# Vario_Kobo.net
KiCad netlist of a schematic drawn in EAGLE
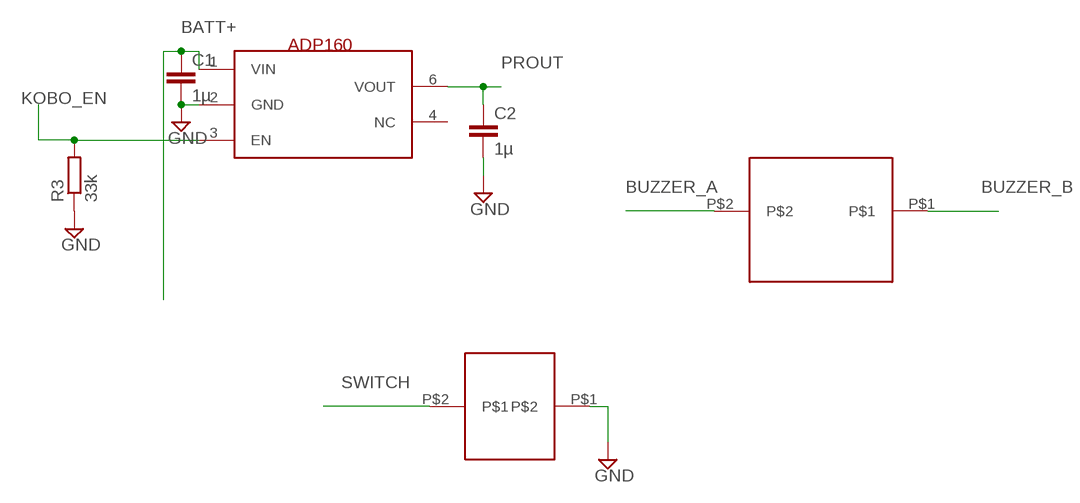
[diagram p0: schematic, sheet 1]
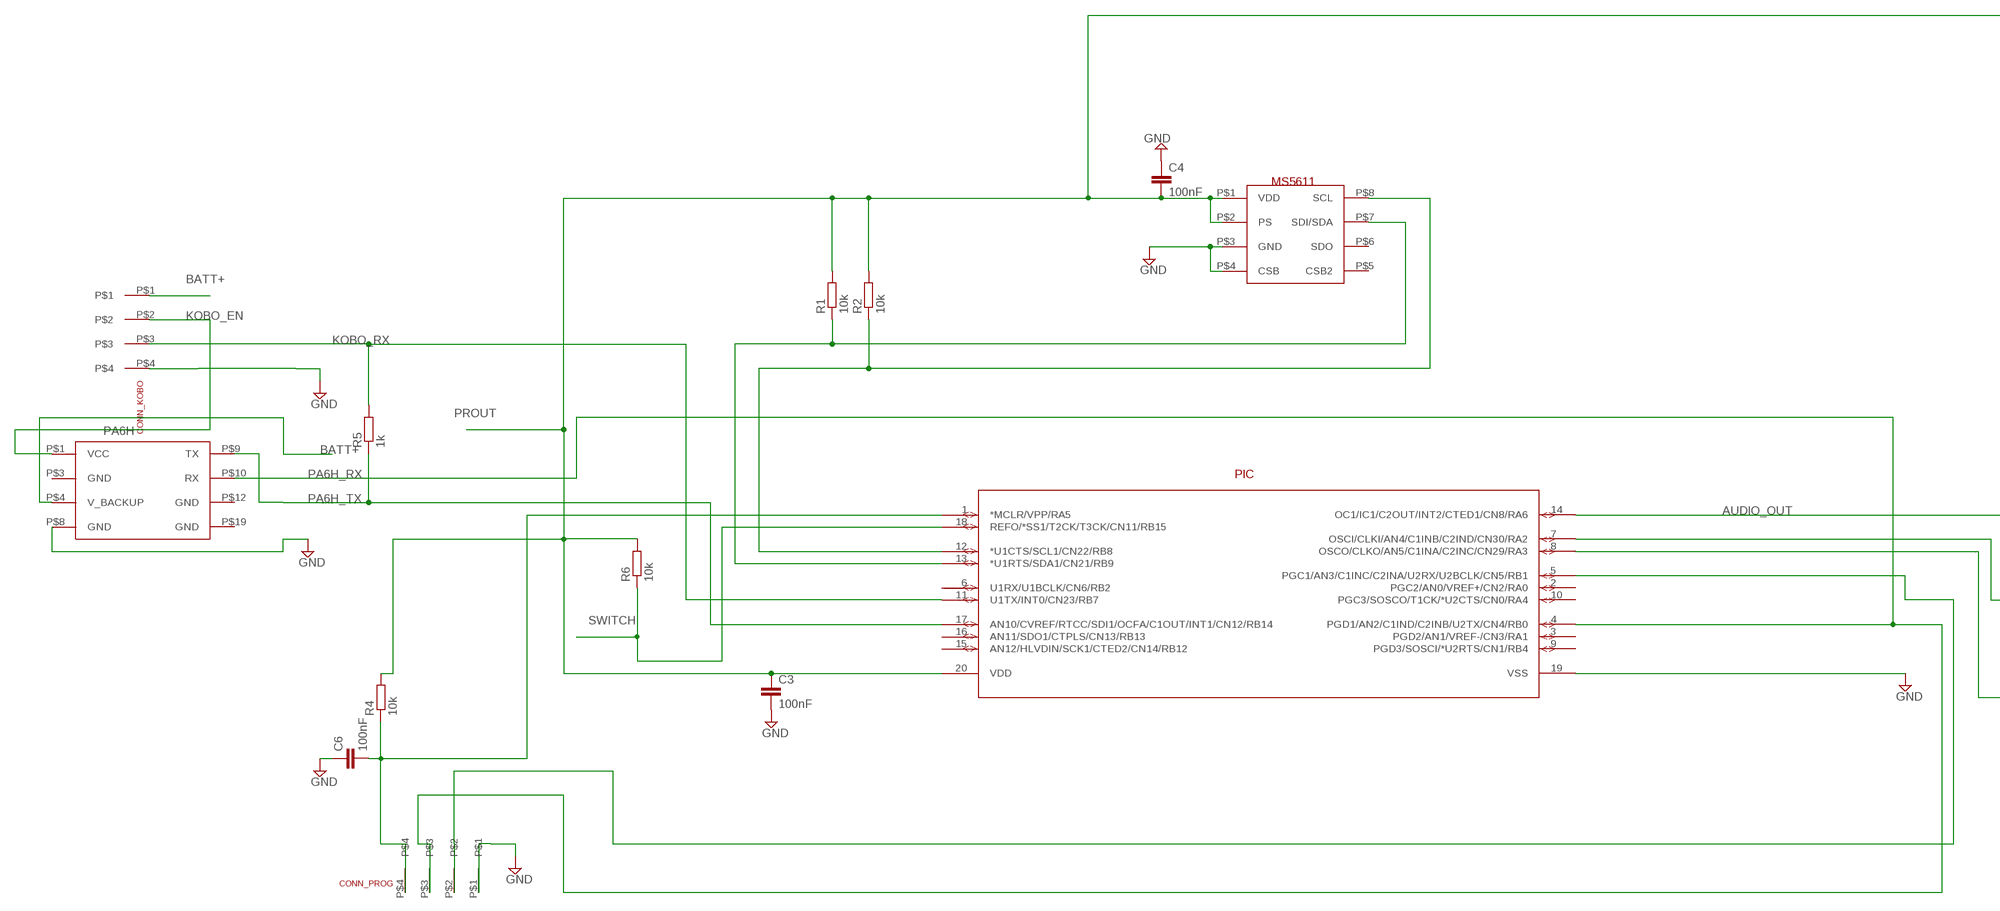
[diagram p1: schematic, sheet 2, part 1 of 2]
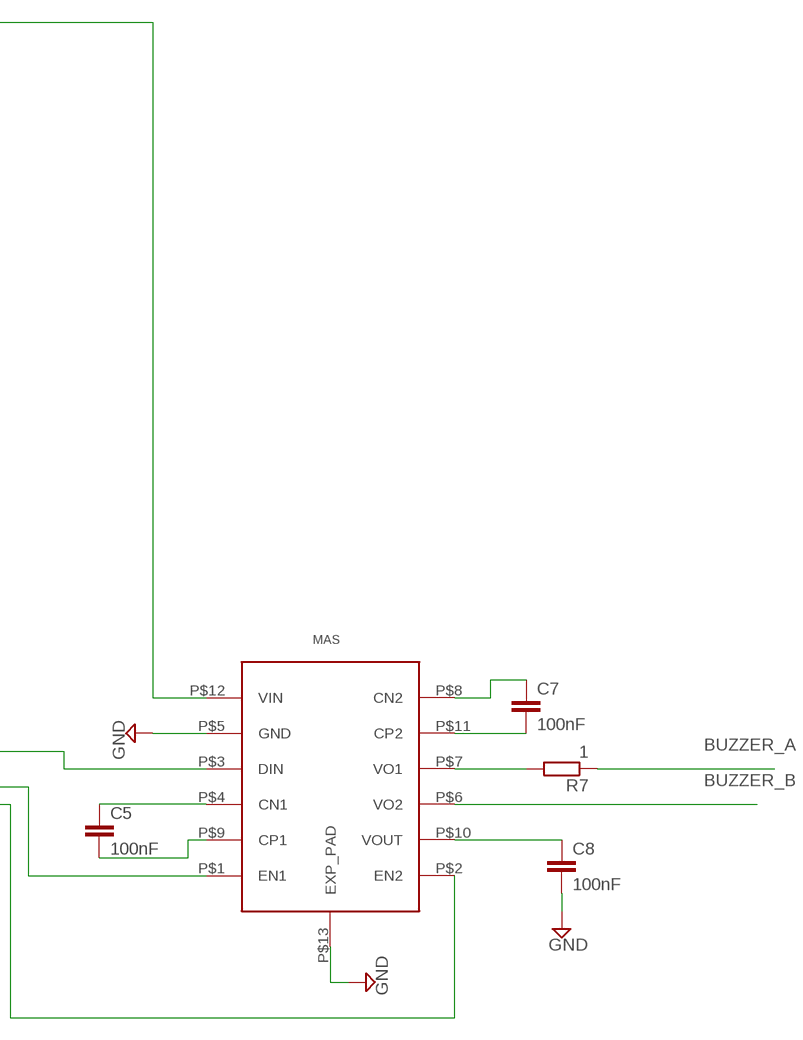
[diagram p2: schematic, sheet 2, part 2 of 2]

(export (version "E")
  (design (tool "Eeschema 10.0.6"))
  (components
    (comp (ref "ADP160")
      (value "ADP160/161/162/163")
      (footprint "eagle-import:TSOT23-6_DDC")
      (libsource (lib "eagle-import") (part "ADP160/161/162/163"))
    )
    (comp (ref "BUTTON")
      (value "SMS_J_LEAD")
      (footprint "eagle-import:SMS_J_LEAD")
      (libsource (lib "eagle-import") (part "SMS_J_LEAD"))
    )
    (comp (ref "BUZZER")
      (value "PKLCS1212E2000-R1")
      (footprint "eagle-import:PKLCS1212E2000-R1-SMD")
      (libsource (lib "eagle-import") (part "PKLCS1212E2000-R1"))
    )
    (comp (ref "C1")
      (value "1µ")
      (footprint "eagle-import:C0603")
      (libsource (lib "eagle-import") (part "C-EUC0603"))
    )
    (comp (ref "C2")
      (value "1µ")
      (footprint "eagle-import:C0603")
      (libsource (lib "eagle-import") (part "C-EUC0603"))
    )
    (comp (ref "R3")
      (value "33k")
      (footprint "eagle-import:R0603")
      (libsource (lib "eagle-import") (part "R-EU_R0603"))
    )
    (comp (ref "C3")
      (value "100nF")
      (footprint "eagle-import:C0603")
      (libsource (lib "eagle-import") (part "C-EUC0603"))
    )
    (comp (ref "C4")
      (value "100nF")
      (footprint "eagle-import:C0603")
      (libsource (lib "eagle-import") (part "C-EUC0603"))
    )
    (comp (ref "C5")
      (value "100nF")
      (footprint "eagle-import:C0603")
      (libsource (lib "eagle-import") (part "C-EUC0603"))
    )
    (comp (ref "C6")
      (value "100nF")
      (footprint "eagle-import:C0603")
      (libsource (lib "eagle-import") (part "C-EUC0603"))
    )
    (comp (ref "C7")
      (value "100nF")
      (footprint "eagle-import:C0603")
      (libsource (lib "eagle-import") (part "C-EUC0603"))
    )
    (comp (ref "C8")
      (value "100nF")
      (footprint "eagle-import:C0603")
      (libsource (lib "eagle-import") (part "C-EUC0603"))
    )
    (comp (ref "CONN_KOBO")
      (value "PICO-EZMATE4")
      (footprint "eagle-import:PICO-EZMATE4-PCB")
      (libsource (lib "eagle-import") (part "PICO-EZMATE4"))
    )
    (comp (ref "CONN_PROG")
      (value "PICO-EZMATE4")
      (footprint "eagle-import:PICO-EZMATE4-PCB")
      (libsource (lib "eagle-import") (part "PICO-EZMATE4"))
    )
    (comp (ref "MAS")
      (value "MAS6240")
      (footprint "eagle-import:QFN12_3X3")
      (libsource (lib "eagle-import") (part "MAS6240"))
    )
    (comp (ref "MS5611")
      (value "MS5607PACKAGED")
      (footprint "eagle-import:MS5607-02BA03")
      (libsource (lib "eagle-import") (part "MS5607PACKAGED"))
    )
    (comp (ref "PA6H")
      (value "PA6H")
      (footprint "eagle-import:PA6H_PRINT")
      (libsource (lib "eagle-import") (part "PA6H"))
    )
    (comp (ref "PIC")
      (value "PIC24F16KA101-X_")
      (footprint "eagle-import:SSOP20_MC")
      (libsource (lib "eagle-import") (part "PIC24F16KA101-X_"))
    )
    (comp (ref "R1")
      (value "10k")
      (footprint "eagle-import:R0603")
      (libsource (lib "eagle-import") (part "R-EU_R0603"))
    )
    (comp (ref "R2")
      (value "10k")
      (footprint "eagle-import:R0603")
      (libsource (lib "eagle-import") (part "R-EU_R0603"))
    )
    (comp (ref "R4")
      (value "10k")
      (footprint "eagle-import:R0603")
      (libsource (lib "eagle-import") (part "R-EU_R0603"))
    )
    (comp (ref "R5")
      (value "1k")
      (footprint "eagle-import:R0603")
      (libsource (lib "eagle-import") (part "R-EU_R0603"))
    )
    (comp (ref "R6")
      (value "10k")
      (footprint "eagle-import:R0603")
      (libsource (lib "eagle-import") (part "R-EU_R0603"))
    )
    (comp (ref "R7")
      (value "1")
      (footprint "eagle-import:R0603")
      (libsource (lib "eagle-import") (part "R-EU_R0603"))
    )
  )
  (nets
    (net (code "1") (name "AUDIO_OUT") (class "Default")
      (node (ref "MAS") (pin "P$3") (pinfunction "DIN_P$3") (pintype "bidirectional"))
      (node (ref "PIC") (pin "14") (pinfunction "OC1/IC1/C2OUT/INT2/CTED1/CN8/RA6_14") (pintype "passive"))
    )
    (net (code "2") (name "BATT+") (class "Default")
      (node (ref "ADP160") (pin "1") (pinfunction "VIN_1") (pintype "tri_state"))
      (node (ref "C1") (pin "1") (pinfunction "1_1") (pintype "passive"))
      (node (ref "CONN_KOBO") (pin "P$1") (pinfunction "P$1_P$1") (pintype "bidirectional"))
      (node (ref "PA6H") (pin "P$4") (pinfunction "V_BACKUP_P$4") (pintype "bidirectional"))
    )
    (net (code "3") (name "BUZZER_A") (class "Default")
      (node (ref "BUZZER") (pin "P$2") (pinfunction "P$2_P$2") (pintype "bidirectional"))
      (node (ref "R7") (pin "1") (pinfunction "1_1") (pintype "passive"))
    )
    (net (code "4") (name "BUZZER_B") (class "Default")
      (node (ref "BUZZER") (pin "P$1") (pinfunction "P$1_P$1") (pintype "bidirectional"))
      (node (ref "MAS") (pin "P$6") (pinfunction "VO2_P$6") (pintype "bidirectional"))
    )
    (net (code "5") (name "GND") (class "Default")
      (node (ref "ADP160") (pin "2") (pinfunction "GND_2") (pintype "power_in"))
      (node (ref "BUTTON") (pin "P$1") (pinfunction "P$2_P$1") (pintype "bidirectional"))
      (node (ref "C1") (pin "2") (pinfunction "2_2") (pintype "passive"))
      (node (ref "C2") (pin "2") (pinfunction "2_2") (pintype "passive"))
      (node (ref "C3") (pin "2") (pinfunction "2_2") (pintype "passive"))
      (node (ref "C4") (pin "1") (pinfunction "1_1") (pintype "passive"))
      (node (ref "C6") (pin "1") (pinfunction "1_1") (pintype "passive"))
      (node (ref "C8") (pin "2") (pinfunction "2_2") (pintype "passive"))
      (node (ref "CONN_KOBO") (pin "P$4") (pinfunction "P$4_P$4") (pintype "bidirectional"))
      (node (ref "CONN_PROG") (pin "P$1") (pinfunction "P$1_P$1") (pintype "bidirectional"))
      (node (ref "MAS") (pin "P$13") (pinfunction "EXP_PAD_P$13") (pintype "bidirectional"))
      (node (ref "MAS") (pin "P$5") (pinfunction "GND_P$5") (pintype "bidirectional"))
      (node (ref "MS5611") (pin "P$3") (pinfunction "GND_P$3") (pintype "power_in"))
      (node (ref "MS5611") (pin "P$4") (pinfunction "CSB_P$4") (pintype "input"))
      (node (ref "PA6H") (pin "P$8") (pinfunction "GND_P$8") (pintype "bidirectional"))
      (node (ref "PIC") (pin "19") (pinfunction "VSS_19") (pintype "passive"))
      (node (ref "R3") (pin "1") (pinfunction "1_1") (pintype "passive"))
    )
    (net (code "6") (name "KOBO_EN") (class "Default")
      (node (ref "ADP160") (pin "3") (pinfunction "EN_3") (pintype "input"))
      (node (ref "CONN_KOBO") (pin "P$2") (pinfunction "P$2_P$2") (pintype "bidirectional"))
      (node (ref "PA6H") (pin "P$1") (pinfunction "VCC_P$1") (pintype "bidirectional"))
      (node (ref "R3") (pin "2") (pinfunction "2_2") (pintype "passive"))
    )
    (net (code "7") (name "KOBO_RX") (class "Default")
      (node (ref "CONN_KOBO") (pin "P$3") (pinfunction "P$3_P$3") (pintype "bidirectional"))
      (node (ref "PIC") (pin "11") (pinfunction "U1TX/INT0/CN23/RB7_11") (pintype "passive"))
      (node (ref "R5") (pin "2") (pinfunction "2_2") (pintype "passive"))
    )
    (net (code "8") (name "Net-(MAS-CN1)") (class "Default")
      (node (ref "C5") (pin "1") (pinfunction "1_1") (pintype "passive"))
      (node (ref "MAS") (pin "P$4") (pinfunction "CN1_P$4") (pintype "bidirectional"))
    )
    (net (code "9") (name "Net-(MAS-CN2)") (class "Default")
      (node (ref "C7") (pin "1") (pinfunction "1_1") (pintype "passive"))
      (node (ref "MAS") (pin "P$8") (pinfunction "CN2_P$8") (pintype "bidirectional"))
    )
    (net (code "10") (name "Net-(MAS-CP1)") (class "Default")
      (node (ref "C5") (pin "2") (pinfunction "2_2") (pintype "passive"))
      (node (ref "MAS") (pin "P$9") (pinfunction "CP1_P$9") (pintype "bidirectional"))
    )
    (net (code "11") (name "Net-(MAS-CP2)") (class "Default")
      (node (ref "C7") (pin "2") (pinfunction "2_2") (pintype "passive"))
      (node (ref "MAS") (pin "P$11") (pinfunction "CP2_P$11") (pintype "bidirectional"))
    )
    (net (code "12") (name "Net-(MAS-EN1)") (class "Default")
      (node (ref "MAS") (pin "P$1") (pinfunction "EN1_P$1") (pintype "bidirectional"))
      (node (ref "PIC") (pin "7") (pinfunction "OSCI/CLKI/AN4/C1INB/C2IND/CN30/RA2_7") (pintype "passive"))
    )
    (net (code "13") (name "Net-(MAS-EN2)") (class "Default")
      (node (ref "MAS") (pin "P$2") (pinfunction "EN2_P$2") (pintype "bidirectional"))
      (node (ref "PIC") (pin "8") (pinfunction "OSCO/CLKO/AN5/C1INA/C2INC/CN29/RA3_8") (pintype "passive"))
    )
    (net (code "14") (name "Net-(MAS-VO1)") (class "Default")
      (node (ref "MAS") (pin "P$7") (pinfunction "VO1_P$7") (pintype "bidirectional"))
      (node (ref "R7") (pin "2") (pinfunction "2_2") (pintype "passive"))
    )
    (net (code "15") (name "Net-(MAS-VOUT)") (class "Default")
      (node (ref "C8") (pin "1") (pinfunction "1_1") (pintype "passive"))
      (node (ref "MAS") (pin "P$10") (pinfunction "VOUT_P$10") (pintype "bidirectional"))
    )
    (net (code "16") (name "Net-(MS5611-SCL)") (class "Default")
      (node (ref "MS5611") (pin "P$8") (pinfunction "SCL_P$8") (pintype "input"))
      (node (ref "PIC") (pin "12") (pinfunction "*U1CTS/SCL1/CN22/RB8_12") (pintype "passive"))
      (node (ref "R2") (pin "1") (pinfunction "1_1") (pintype "passive"))
    )
    (net (code "17") (name "Net-(MS5611-SDI{slash}SDA)") (class "Default")
      (node (ref "MS5611") (pin "P$7") (pinfunction "SDI/SDA_P$7") (pintype "bidirectional"))
      (node (ref "PIC") (pin "13") (pinfunction "*U1RTS/SDA1/CN21/RB9_13") (pintype "passive"))
      (node (ref "R1") (pin "1") (pinfunction "1_1") (pintype "passive"))
    )
    (net (code "18") (name "Net-(PIC-*MCLR{slash}VPP{slash}RA5)") (class "Default")
      (node (ref "C6") (pin "2") (pinfunction "2_2") (pintype "passive"))
      (node (ref "CONN_PROG") (pin "P$4") (pinfunction "P$4_P$4") (pintype "bidirectional"))
      (node (ref "PIC") (pin "1") (pinfunction "*MCLR/VPP/RA5_1") (pintype "passive"))
      (node (ref "R4") (pin "1") (pinfunction "1_1") (pintype "passive"))
    )
    (net (code "19") (name "Net-(PIC-PGC1{slash}AN3{slash}C1INC{slash}C2INA{slash}U2RX{slash}U2BCLK{slash}CN5{slash}RB1)") (class "Default")
      (node (ref "CONN_PROG") (pin "P$2") (pinfunction "P$2_P$2") (pintype "bidirectional"))
      (node (ref "PIC") (pin "5") (pinfunction "PGC1/AN3/C1INC/C2INA/U2RX/U2BCLK/CN5/RB1_5") (pintype "passive"))
    )
    (net (code "20") (name "PA6H_RX") (class "Default")
      (node (ref "CONN_PROG") (pin "P$3") (pinfunction "P$3_P$3") (pintype "bidirectional"))
      (node (ref "PA6H") (pin "P$10") (pinfunction "RX_P$10") (pintype "bidirectional"))
      (node (ref "PIC") (pin "4") (pinfunction "PGD1/AN2/C1IND/C2INB/U2TX/CN4/RB0_4") (pintype "passive"))
    )
    (net (code "21") (name "PA6H_TX") (class "Default")
      (node (ref "PA6H") (pin "P$9") (pinfunction "TX_P$9") (pintype "bidirectional"))
      (node (ref "PIC") (pin "17") (pinfunction "AN10/CVREF/RTCC/SDI1/OCFA/C1OUT/INT1/CN12/RB14_17") (pintype "passive"))
      (node (ref "R5") (pin "1") (pinfunction "1_1") (pintype "passive"))
    )
    (net (code "22") (name "PROUT") (class "Default")
      (node (ref "ADP160") (pin "6") (pinfunction "VOUT_6") (pintype "bidirectional"))
      (node (ref "C2") (pin "1") (pinfunction "1_1") (pintype "passive"))
      (node (ref "C3") (pin "1") (pinfunction "1_1") (pintype "passive"))
      (node (ref "C4") (pin "2") (pinfunction "2_2") (pintype "passive"))
      (node (ref "MAS") (pin "P$12") (pinfunction "VIN_P$12") (pintype "bidirectional"))
      (node (ref "MS5611") (pin "P$1") (pinfunction "VDD_P$1") (pintype "power_in"))
      (node (ref "MS5611") (pin "P$2") (pinfunction "PS_P$2") (pintype "input"))
      (node (ref "PIC") (pin "20") (pinfunction "VDD_20") (pintype "passive"))
      (node (ref "R1") (pin "2") (pinfunction "2_2") (pintype "passive"))
      (node (ref "R2") (pin "2") (pinfunction "2_2") (pintype "passive"))
      (node (ref "R4") (pin "2") (pinfunction "2_2") (pintype "passive"))
      (node (ref "R6") (pin "2") (pinfunction "2_2") (pintype "passive"))
    )
    (net (code "23") (name "SWITCH") (class "Default")
      (node (ref "BUTTON") (pin "P$2") (pinfunction "P$1_P$2") (pintype "bidirectional"))
      (node (ref "PIC") (pin "18") (pinfunction "REFO/*SS1/T2CK/T3CK/CN11/RB15_18") (pintype "passive"))
      (node (ref "R6") (pin "1") (pinfunction "1_1") (pintype "passive"))
    )
    (net (code "24") (name "unconnected-(ADP160-NC-Pad4)") (class "Default")
      (node (ref "ADP160") (pin "4") (pinfunction "NC_4") (pintype "no_connect"))
    )
    (net (code "25") (name "unconnected-(MS5611-CSB2-PadP$5)") (class "Default")
      (node (ref "MS5611") (pin "P$5") (pinfunction "CSB2_P$5") (pintype "input"))
    )
    (net (code "26") (name "unconnected-(MS5611-SDO-PadP$6)") (class "Default")
      (node (ref "MS5611") (pin "P$6") (pinfunction "SDO_P$6") (pintype "output"))
    )
    (net (code "27") (name "unconnected-(PA6H-GND-PadP$3)") (class "Default")
      (node (ref "PA6H") (pin "P$3") (pinfunction "GND_P$3") (pintype "bidirectional"))
    )
    (net (code "28") (name "unconnected-(PA6H-GND-PadP$12)") (class "Default")
      (node (ref "PA6H") (pin "P$12") (pinfunction "GND_P$12") (pintype "bidirectional"))
    )
    (net (code "29") (name "unconnected-(PA6H-GND-PadP$19)") (class "Default")
      (node (ref "PA6H") (pin "P$19") (pinfunction "GND_P$19") (pintype "bidirectional"))
    )
    (net (code "30") (name "unconnected-(PIC-AN11{slash}SDO1{slash}CTPLS{slash}CN13{slash}RB13-Pad16)") (class "Default")
      (node (ref "PIC") (pin "16") (pinfunction "AN11/SDO1/CTPLS/CN13/RB13_16") (pintype "passive"))
    )
    (net (code "31") (name "unconnected-(PIC-AN12{slash}HLVDIN{slash}SCK1{slash}CTED2{slash}CN14{slash}RB12-Pad15)") (class "Default")
      (node (ref "PIC") (pin "15") (pinfunction "AN12/HLVDIN/SCK1/CTED2/CN14/RB12_15") (pintype "passive"))
    )
    (net (code "32") (name "unconnected-(PIC-PGC2{slash}AN0{slash}VREF+{slash}CN2{slash}RA0-Pad2)") (class "Default")
      (node (ref "PIC") (pin "2") (pinfunction "PGC2/AN0/VREF+/CN2/RA0_2") (pintype "passive"))
    )
    (net (code "33") (name "unconnected-(PIC-PGC3{slash}SOSCO{slash}T1CK{slash}*U2CTS{slash}CN0{slash}RA4-Pad10)") (class "Default")
      (node (ref "PIC") (pin "10") (pinfunction "PGC3/SOSCO/T1CK/*U2CTS/CN0/RA4_10") (pintype "passive"))
    )
    (net (code "34") (name "unconnected-(PIC-PGD2{slash}AN1{slash}VREF-{slash}CN3{slash}RA1-Pad3)") (class "Default")
      (node (ref "PIC") (pin "3") (pinfunction "PGD2/AN1/VREF-/CN3/RA1_3") (pintype "passive"))
    )
    (net (code "35") (name "unconnected-(PIC-PGD3{slash}SOSCI{slash}*U2RTS{slash}CN1{slash}RB4-Pad9)") (class "Default")
      (node (ref "PIC") (pin "9") (pinfunction "PGD3/SOSCI/*U2RTS/CN1/RB4_9") (pintype "passive"))
    )
    (net (code "36") (name "unconnected-(PIC-U1RX{slash}U1BCLK{slash}CN6{slash}RB2-Pad6)") (class "Default")
      (node (ref "PIC") (pin "6") (pinfunction "U1RX/U1BCLK/CN6/RB2_6") (pintype "passive"))
    )
  )
)
